# PDM_Final.net
KiCad netlist of a schematic drawn in EAGLE
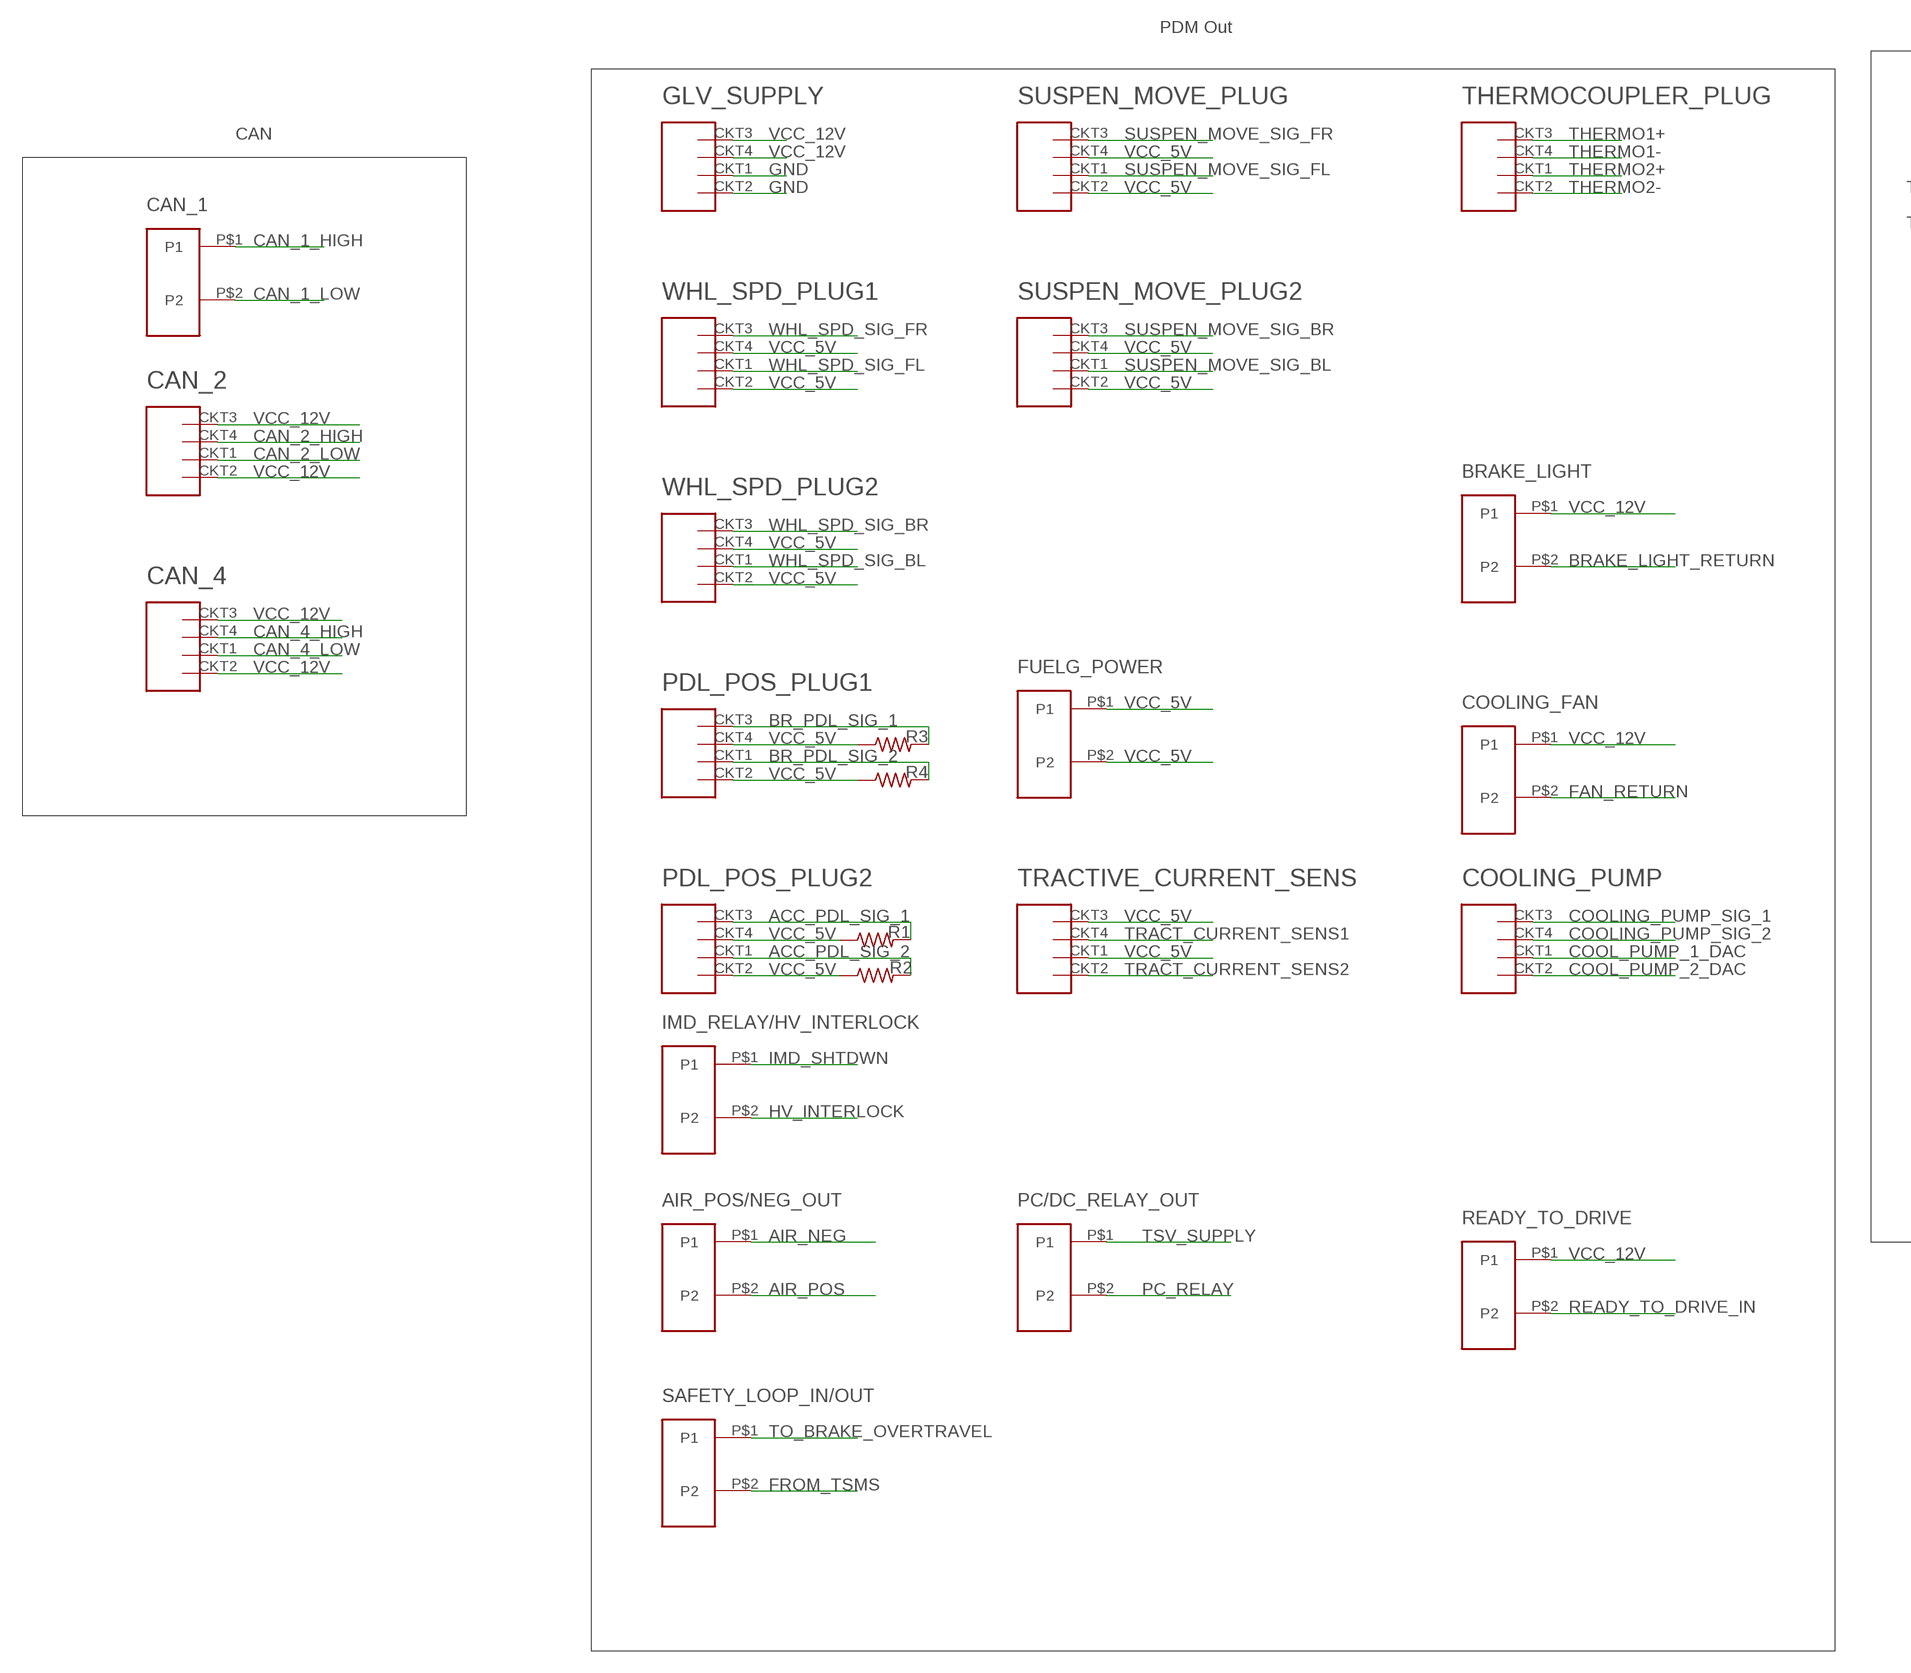
[diagram p0: schematic, sheet 1, part 1 of 2]
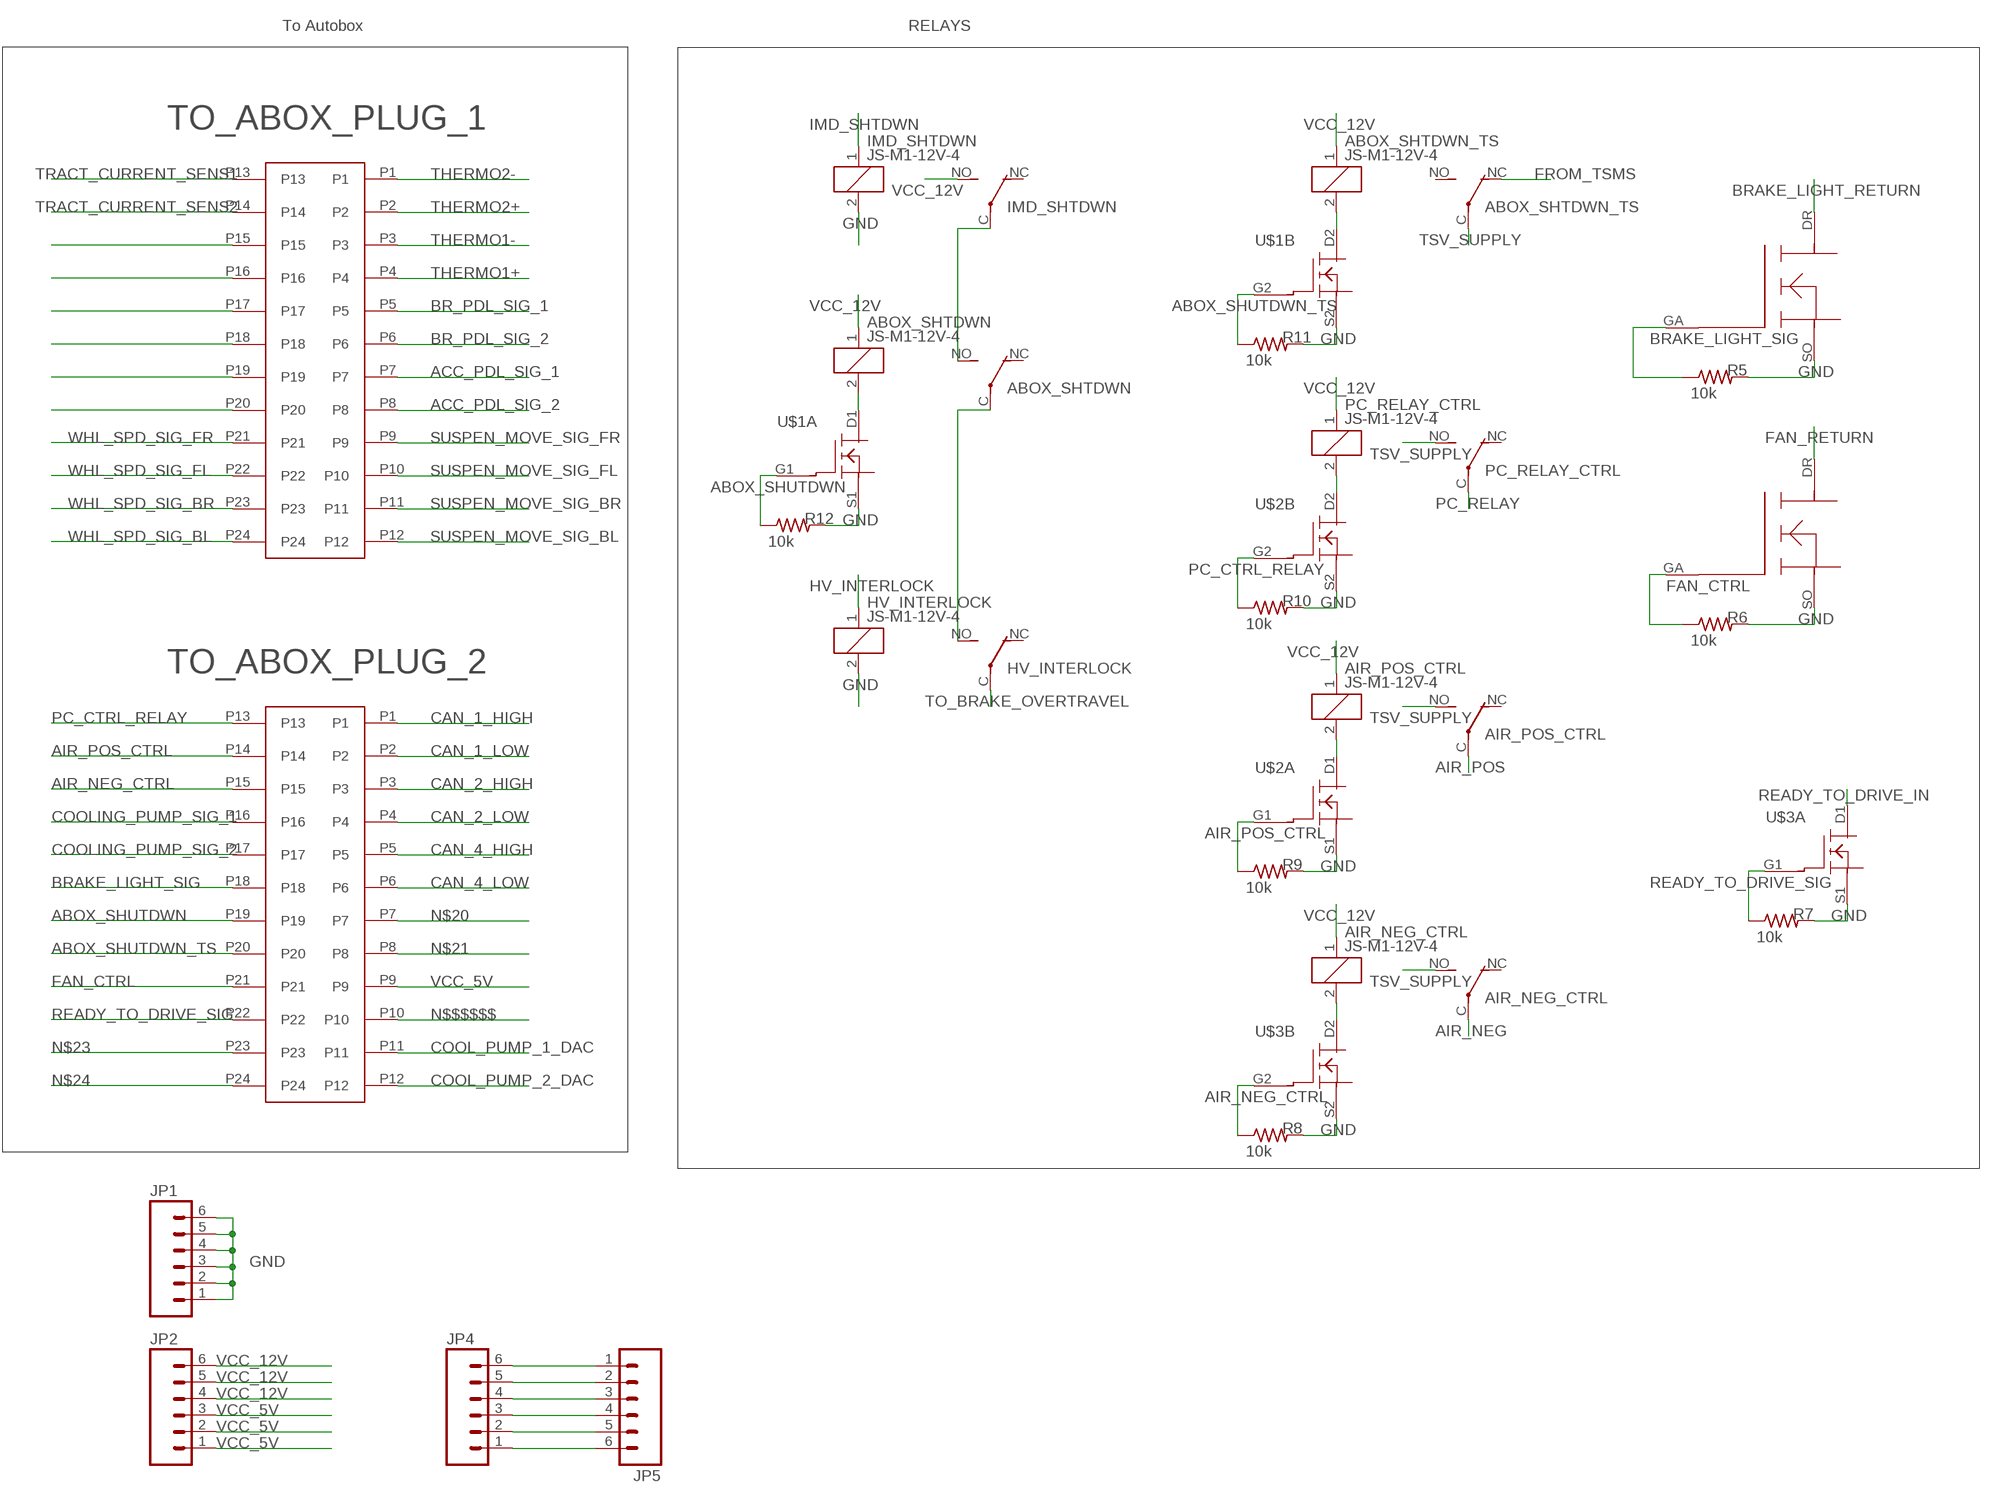
[diagram p1: schematic, sheet 1, part 2 of 2]

(export (version "E")
  (design (tool "Eeschema 10.0.6"))
  (components
    (comp (ref "ABOX_SHTDWN")
      (value "JS-M1-12V-4")
      (footprint "eagle-import:JS-M")
      (fields (field (name "MPN") "JSM1-12V-4"))
      (libsource (lib "eagle-import") (part "JS-M1-12V-4"))
    )
    (comp (ref "ABOX_SHTDWN_TS")
      (value "JS-M1-12V-4")
      (footprint "eagle-import:JS-M")
      (fields (field (name "MPN") "JSM1-12V-4"))
      (libsource (lib "eagle-import") (part "JS-M1-12V-4"))
    )
    (comp (ref "AIR_NEG_CTRL")
      (value "JS-M1-12V-4")
      (footprint "eagle-import:JS-M")
      (fields (field (name "MPN") "JSM1-12V-4"))
      (libsource (lib "eagle-import") (part "JS-M1-12V-4"))
    )
    (comp (ref "AIR_POS/NEG_OUT")
      (value "MINIFIT_2PIN")
      (footprint "eagle-import:2PIN_MOLEXMINIFIT")
      (libsource (lib "eagle-import") (part "MINIFIT_2PIN"))
    )
    (comp (ref "AIR_POS_CTRL")
      (value "JS-M1-12V-4")
      (footprint "eagle-import:JS-M")
      (fields (field (name "MPN") "JSM1-12V-4"))
      (libsource (lib "eagle-import") (part "JS-M1-12V-4"))
    )
    (comp (ref "BRAKE_LIGHT")
      (value "MINIFIT_2PIN")
      (footprint "eagle-import:2PIN_MOLEXMINIFIT")
      (libsource (lib "eagle-import") (part "MINIFIT_2PIN"))
    )
    (comp (ref "CAN_1")
      (value "MINIFIT_2PIN")
      (footprint "eagle-import:2PIN_MOLEXMINIFIT")
      (libsource (lib "eagle-import") (part "MINIFIT_2PIN"))
    )
    (comp (ref "CAN_2")
      (value "MHYBRIDMOLEX")
      (footprint "eagle-import:MOLEXMINIFIT6")
      (libsource (lib "eagle-import") (part "MHYBRIDMOLEX"))
    )
    (comp (ref "CAN_4")
      (value "MHYBRIDMOLEX")
      (footprint "eagle-import:MOLEXMINIFIT6")
      (libsource (lib "eagle-import") (part "MHYBRIDMOLEX"))
    )
    (comp (ref "COOLING_FAN")
      (value "MINIFIT_2PIN")
      (footprint "eagle-import:2PIN_MOLEXMINIFIT")
      (libsource (lib "eagle-import") (part "MINIFIT_2PIN"))
    )
    (comp (ref "COOLING_PUMP")
      (value "MHYBRIDMOLEX")
      (footprint "eagle-import:MOLEXMINIFIT6")
      (libsource (lib "eagle-import") (part "MHYBRIDMOLEX"))
    )
    (comp (ref "FUELG_POWER")
      (value "MINIFIT_2PIN")
      (footprint "eagle-import:2PIN_MOLEXMINIFIT")
      (libsource (lib "eagle-import") (part "MINIFIT_2PIN"))
    )
    (comp (ref "GLV_SUPPLY")
      (value "MHYBRIDMOLEX")
      (footprint "eagle-import:MOLEXMINIFIT6")
      (libsource (lib "eagle-import") (part "MHYBRIDMOLEX"))
    )
    (comp (ref "HV_INTERLOCK")
      (value "JS-M1-12V-4")
      (footprint "eagle-import:JS-M")
      (fields (field (name "MPN") "JSM1-12V-4"))
      (libsource (lib "eagle-import") (part "JS-M1-12V-4"))
    )
    (comp (ref "IMD_RELAY/HV_INTERLOCK")
      (value "MINIFIT_2PIN")
      (footprint "eagle-import:2PIN_MOLEXMINIFIT")
      (libsource (lib "eagle-import") (part "MINIFIT_2PIN"))
    )
    (comp (ref "IMD_SHTDWN")
      (value "JS-M1-12V-4")
      (footprint "eagle-import:JS-M")
      (fields (field (name "MPN") "JSM1-12V-4"))
      (libsource (lib "eagle-import") (part "JS-M1-12V-4"))
    )
    (comp (ref "JP1")
      (value "M06LOCK")
      (footprint "eagle-import:1X06_LOCK")
      (libsource (lib "eagle-import") (part "M06LOCK"))
    )
    (comp (ref "JP2")
      (value "M06LOCK")
      (footprint "eagle-import:1X06_LOCK")
      (libsource (lib "eagle-import") (part "M06LOCK"))
    )
    (comp (ref "JP4")
      (value "M06LOCK")
      (footprint "eagle-import:1X06_LOCK")
      (libsource (lib "eagle-import") (part "M06LOCK"))
    )
    (comp (ref "JP5")
      (value "M06LOCK")
      (footprint "eagle-import:1X06_LOCK")
      (libsource (lib "eagle-import") (part "M06LOCK"))
    )
    (comp (ref "PC/DC_RELAY_OUT")
      (value "MINIFIT_2PIN")
      (footprint "eagle-import:2PIN_MOLEXMINIFIT")
      (libsource (lib "eagle-import") (part "MINIFIT_2PIN"))
    )
    (comp (ref "PC_RELAY_CTRL")
      (value "JS-M1-12V-4")
      (footprint "eagle-import:JS-M")
      (fields (field (name "MPN") "JSM1-12V-4"))
      (libsource (lib "eagle-import") (part "JS-M1-12V-4"))
    )
    (comp (ref "PDL_POS_PLUG1")
      (value "MHYBRIDMOLEX")
      (footprint "eagle-import:MOLEXMINIFIT6")
      (libsource (lib "eagle-import") (part "MHYBRIDMOLEX"))
    )
    (comp (ref "PDL_POS_PLUG2")
      (value "MHYBRIDMOLEX")
      (footprint "eagle-import:MOLEXMINIFIT6")
      (libsource (lib "eagle-import") (part "MHYBRIDMOLEX"))
    )
    (comp (ref "R1")
      (value "R-US_0204/2V")
      (footprint "eagle-import:0204V")
      (libsource (lib "eagle-import") (part "R-US_0204/2V"))
    )
    (comp (ref "R2")
      (value "R-US_0204/2V")
      (footprint "eagle-import:0204V")
      (libsource (lib "eagle-import") (part "R-US_0204/2V"))
    )
    (comp (ref "R3")
      (value "R-US_0204/2V")
      (footprint "eagle-import:0204V")
      (libsource (lib "eagle-import") (part "R-US_0204/2V"))
    )
    (comp (ref "R4")
      (value "R-US_0204/2V")
      (footprint "eagle-import:0204V")
      (libsource (lib "eagle-import") (part "R-US_0204/2V"))
    )
    (comp (ref "R5")
      (value "10k")
      (footprint "eagle-import:0204V")
      (libsource (lib "eagle-import") (part "R-US_0204/2V"))
    )
    (comp (ref "R6")
      (value "10k")
      (footprint "eagle-import:0204V")
      (libsource (lib "eagle-import") (part "R-US_0204/2V"))
    )
    (comp (ref "R7")
      (value "10k")
      (footprint "eagle-import:0204V")
      (libsource (lib "eagle-import") (part "R-US_0204/2V"))
    )
    (comp (ref "R8")
      (value "10k")
      (footprint "eagle-import:0204V")
      (libsource (lib "eagle-import") (part "R-US_0204/2V"))
    )
    (comp (ref "R9")
      (value "10k")
      (footprint "eagle-import:0204V")
      (libsource (lib "eagle-import") (part "R-US_0204/2V"))
    )
    (comp (ref "R10")
      (value "10k")
      (footprint "eagle-import:0204V")
      (libsource (lib "eagle-import") (part "R-US_0204/2V"))
    )
    (comp (ref "R11")
      (value "10k")
      (footprint "eagle-import:0204V")
      (libsource (lib "eagle-import") (part "R-US_0204/2V"))
    )
    (comp (ref "R12")
      (value "10k")
      (footprint "eagle-import:0204V")
      (libsource (lib "eagle-import") (part "R-US_0204/2V"))
    )
    (comp (ref "READY_TO_DRIVE")
      (value "MINIFIT_2PIN")
      (footprint "eagle-import:2PIN_MOLEXMINIFIT")
      (libsource (lib "eagle-import") (part "MINIFIT_2PIN"))
    )
    (comp (ref "SAFETY_LOOP_IN/OUT")
      (value "MINIFIT_2PIN")
      (footprint "eagle-import:2PIN_MOLEXMINIFIT")
      (libsource (lib "eagle-import") (part "MINIFIT_2PIN"))
    )
    (comp (ref "SUSPEN_MOVE_PLUG")
      (value "MHYBRIDMOLEX")
      (footprint "eagle-import:MOLEXMINIFIT6")
      (libsource (lib "eagle-import") (part "MHYBRIDMOLEX"))
    )
    (comp (ref "SUSPEN_MOVE_PLUG2")
      (value "MHYBRIDMOLEX")
      (footprint "eagle-import:MOLEXMINIFIT6")
      (libsource (lib "eagle-import") (part "MHYBRIDMOLEX"))
    )
    (comp (ref "THERMOCOUPLER_PLUG")
      (value "MHYBRIDMOLEX")
      (footprint "eagle-import:MOLEXMINIFIT6")
      (libsource (lib "eagle-import") (part "MHYBRIDMOLEX"))
    )
    (comp (ref "TO_ABOX_PLUG_1")
      (value "24PIN_MOLEX")
      (footprint "eagle-import:24PIN_MOLEX")
      (libsource (lib "eagle-import") (part "24PIN_MOLEX"))
    )
    (comp (ref "TO_ABOX_PLUG_2")
      (value "24PIN_MOLEX")
      (footprint "eagle-import:24PIN_MOLEX")
      (libsource (lib "eagle-import") (part "24PIN_MOLEX"))
    )
    (comp (ref "TRACTIVE_CURRENT_SENS")
      (value "MHYBRIDMOLEX")
      (footprint "eagle-import:MOLEXMINIFIT6")
      (libsource (lib "eagle-import") (part "MHYBRIDMOLEX"))
    )
    (comp (ref "U$1")
      (value "COMBINED_TRANSIS")
      (footprint "eagle-import:TRANSIS_6")
      (libsource (lib "eagle-import") (part "COMBINED_TRANSIS"))
    )
    (comp (ref "U$2")
      (value "COMBINED_TRANSIS")
      (footprint "eagle-import:TRANSIS_6")
      (libsource (lib "eagle-import") (part "COMBINED_TRANSIS"))
    )
    (comp (ref "U$3")
      (value "COMBINED_TRANSIS")
      (footprint "eagle-import:TRANSIS_6")
      (libsource (lib "eagle-import") (part "COMBINED_TRANSIS"))
    )
    (comp (ref "U$4")
      (value "HIGH_AMP_TRANS")
      (footprint "eagle-import:HIGH_AMP_TRANS")
      (libsource (lib "eagle-import") (part "HIGH_AMP_TRANS"))
    )
    (comp (ref "U$5")
      (value "HIGH_AMP_TRANS")
      (footprint "eagle-import:HIGH_AMP_TRANS")
      (libsource (lib "eagle-import") (part "HIGH_AMP_TRANS"))
    )
    (comp (ref "WHL_SPD_PLUG1")
      (value "MHYBRIDMOLEX")
      (footprint "eagle-import:MOLEXMINIFIT6")
      (libsource (lib "eagle-import") (part "MHYBRIDMOLEX"))
    )
    (comp (ref "WHL_SPD_PLUG2")
      (value "MHYBRIDMOLEX")
      (footprint "eagle-import:MOLEXMINIFIT6")
      (libsource (lib "eagle-import") (part "MHYBRIDMOLEX"))
    )
  )
  (nets
    (net (code "1") (name "/ABOX_SHUTDWN") (class "Default")
      (node (ref "R12") (pin "1") (pinfunction "1_1") (pintype "passive"))
      (node (ref "TO_ABOX_PLUG_2") (pin "P19") (pinfunction "P19_P19") (pintype "bidirectional"))
      (node (ref "U$1") (pin "G1") (pinfunction "GA_G1") (pintype "bidirectional"))
    )
    (net (code "2") (name "/ABOX_SHUTDWN_TS") (class "Default")
      (node (ref "R11") (pin "1") (pinfunction "1_1") (pintype "passive"))
      (node (ref "TO_ABOX_PLUG_2") (pin "P20") (pinfunction "P20_P20") (pintype "bidirectional"))
      (node (ref "U$1") (pin "G2") (pinfunction "GA_G2") (pintype "bidirectional"))
    )
    (net (code "3") (name "/ACC_PDL_SIG_1") (class "Default")
      (node (ref "PDL_POS_PLUG2") (pin "CKT3") (pinfunction "V_IN(12)_CKT3") (pintype "bidirectional"))
      (node (ref "R1") (pin "2") (pinfunction "2_2") (pintype "passive"))
      (node (ref "TO_ABOX_PLUG_1") (pin "P7") (pinfunction "P7_P7") (pintype "bidirectional"))
    )
    (net (code "4") (name "/ACC_PDL_SIG_2") (class "Default")
      (node (ref "PDL_POS_PLUG2") (pin "CKT1") (pinfunction "GND_CKT1") (pintype "bidirectional"))
      (node (ref "R2") (pin "2") (pinfunction "2_2") (pintype "passive"))
      (node (ref "TO_ABOX_PLUG_1") (pin "P8") (pinfunction "P8_P8") (pintype "bidirectional"))
    )
    (net (code "5") (name "/AIR_NEG") (class "Default")
      (node (ref "AIR_NEG_CTRL") (pin "C") (pinfunction "P_C") (pintype "passive"))
      (node (ref "AIR_POS/NEG_OUT") (pin "P$1") (pinfunction "P1_P$1") (pintype "bidirectional"))
    )
    (net (code "6") (name "/AIR_NEG_CTRL") (class "Default")
      (node (ref "R8") (pin "1") (pinfunction "1_1") (pintype "passive"))
      (node (ref "TO_ABOX_PLUG_2") (pin "P15") (pinfunction "P15_P15") (pintype "bidirectional"))
      (node (ref "U$3") (pin "G2") (pinfunction "GA_G2") (pintype "bidirectional"))
    )
    (net (code "7") (name "/AIR_POS") (class "Default")
      (node (ref "AIR_POS/NEG_OUT") (pin "P$2") (pinfunction "P2_P$2") (pintype "bidirectional"))
      (node (ref "AIR_POS_CTRL") (pin "C") (pinfunction "P_C") (pintype "passive"))
    )
    (net (code "8") (name "/AIR_POS_CTRL") (class "Default")
      (node (ref "R9") (pin "1") (pinfunction "1_1") (pintype "passive"))
      (node (ref "TO_ABOX_PLUG_2") (pin "P14") (pinfunction "P14_P14") (pintype "bidirectional"))
      (node (ref "U$2") (pin "G1") (pinfunction "GA_G1") (pintype "bidirectional"))
    )
    (net (code "9") (name "/BRAKE_LIGHT_RETURN") (class "Default")
      (node (ref "BRAKE_LIGHT") (pin "P$2") (pinfunction "P2_P$2") (pintype "bidirectional"))
      (node (ref "U$4") (pin "DR") (pinfunction "DR_DR") (pintype "bidirectional"))
    )
    (net (code "10") (name "/BRAKE_LIGHT_SIG") (class "Default")
      (node (ref "R5") (pin "1") (pinfunction "1_1") (pintype "passive"))
      (node (ref "TO_ABOX_PLUG_2") (pin "P18") (pinfunction "P18_P18") (pintype "bidirectional"))
      (node (ref "U$4") (pin "GA") (pinfunction "GA_GA") (pintype "bidirectional"))
    )
    (net (code "11") (name "/BR_PDL_SIG_1") (class "Default")
      (node (ref "PDL_POS_PLUG1") (pin "CKT3") (pinfunction "V_IN(12)_CKT3") (pintype "bidirectional"))
      (node (ref "R3") (pin "2") (pinfunction "2_2") (pintype "passive"))
      (node (ref "TO_ABOX_PLUG_1") (pin "P5") (pinfunction "P5_P5") (pintype "bidirectional"))
    )
    (net (code "12") (name "/BR_PDL_SIG_2") (class "Default")
      (node (ref "PDL_POS_PLUG1") (pin "CKT1") (pinfunction "GND_CKT1") (pintype "bidirectional"))
      (node (ref "R4") (pin "2") (pinfunction "2_2") (pintype "passive"))
      (node (ref "TO_ABOX_PLUG_1") (pin "P6") (pinfunction "P6_P6") (pintype "bidirectional"))
    )
    (net (code "13") (name "/CAN_1_HIGH") (class "Default")
      (node (ref "CAN_1") (pin "P$1") (pinfunction "P1_P$1") (pintype "bidirectional"))
      (node (ref "TO_ABOX_PLUG_2") (pin "P1") (pinfunction "P1_P1") (pintype "bidirectional"))
    )
    (net (code "14") (name "/CAN_1_LOW") (class "Default")
      (node (ref "CAN_1") (pin "P$2") (pinfunction "P2_P$2") (pintype "bidirectional"))
      (node (ref "TO_ABOX_PLUG_2") (pin "P2") (pinfunction "P2_P2") (pintype "bidirectional"))
    )
    (net (code "15") (name "/CAN_2_HIGH") (class "Default")
      (node (ref "CAN_2") (pin "CKT4") (pinfunction "V_IN2(12)_CKT4") (pintype "bidirectional"))
      (node (ref "TO_ABOX_PLUG_2") (pin "P3") (pinfunction "P3_P3") (pintype "bidirectional"))
    )
    (net (code "16") (name "/CAN_2_LOW") (class "Default")
      (node (ref "CAN_2") (pin "CKT1") (pinfunction "GND_CKT1") (pintype "bidirectional"))
      (node (ref "TO_ABOX_PLUG_2") (pin "P4") (pinfunction "P4_P4") (pintype "bidirectional"))
    )
    (net (code "17") (name "/CAN_4_HIGH") (class "Default")
      (node (ref "CAN_4") (pin "CKT4") (pinfunction "V_IN2(12)_CKT4") (pintype "bidirectional"))
      (node (ref "TO_ABOX_PLUG_2") (pin "P5") (pinfunction "P5_P5") (pintype "bidirectional"))
    )
    (net (code "18") (name "/CAN_4_LOW") (class "Default")
      (node (ref "CAN_4") (pin "CKT1") (pinfunction "GND_CKT1") (pintype "bidirectional"))
      (node (ref "TO_ABOX_PLUG_2") (pin "P6") (pinfunction "P6_P6") (pintype "bidirectional"))
    )
    (net (code "19") (name "/COOLING_PUMP_SIG_1") (class "Default")
      (node (ref "COOLING_PUMP") (pin "CKT3") (pinfunction "V_IN(12)_CKT3") (pintype "bidirectional"))
      (node (ref "TO_ABOX_PLUG_2") (pin "P16") (pinfunction "P16_P16") (pintype "bidirectional"))
    )
    (net (code "20") (name "/COOLING_PUMP_SIG_2") (class "Default")
      (node (ref "COOLING_PUMP") (pin "CKT4") (pinfunction "V_IN2(12)_CKT4") (pintype "bidirectional"))
      (node (ref "TO_ABOX_PLUG_2") (pin "P17") (pinfunction "P17_P17") (pintype "bidirectional"))
    )
    (net (code "21") (name "/COOL_PUMP_1_DAC") (class "Default")
      (node (ref "COOLING_PUMP") (pin "CKT1") (pinfunction "GND_CKT1") (pintype "bidirectional"))
      (node (ref "TO_ABOX_PLUG_2") (pin "P11") (pinfunction "P11_P11") (pintype "bidirectional"))
    )
    (net (code "22") (name "/COOL_PUMP_2_DAC") (class "Default")
      (node (ref "COOLING_PUMP") (pin "CKT2") (pinfunction "GND2_CKT2") (pintype "bidirectional"))
      (node (ref "TO_ABOX_PLUG_2") (pin "P12") (pinfunction "P12_P12") (pintype "bidirectional"))
    )
    (net (code "23") (name "/FAN_CTRL") (class "Default")
      (node (ref "R6") (pin "1") (pinfunction "1_1") (pintype "passive"))
      (node (ref "TO_ABOX_PLUG_2") (pin "P21") (pinfunction "P21_P21") (pintype "bidirectional"))
      (node (ref "U$5") (pin "GA") (pinfunction "GA_GA") (pintype "bidirectional"))
    )
    (net (code "24") (name "/FAN_RETURN") (class "Default")
      (node (ref "COOLING_FAN") (pin "P$2") (pinfunction "P2_P$2") (pintype "bidirectional"))
      (node (ref "U$5") (pin "DR") (pinfunction "DR_DR") (pintype "bidirectional"))
    )
    (net (code "25") (name "/FROM_TSMS") (class "Default")
      (node (ref "ABOX_SHTDWN_TS") (pin "NC") (pinfunction "O_NC") (pintype "passive"))
      (node (ref "SAFETY_LOOP_IN/OUT") (pin "P$2") (pinfunction "P2_P$2") (pintype "bidirectional"))
    )
    (net (code "26") (name "/GND") (class "Default")
      (node (ref "GLV_SUPPLY") (pin "CKT1") (pinfunction "GND_CKT1") (pintype "bidirectional"))
      (node (ref "GLV_SUPPLY") (pin "CKT2") (pinfunction "GND2_CKT2") (pintype "bidirectional"))
      (node (ref "HV_INTERLOCK") (pin "2") (pinfunction "2_2") (pintype "passive"))
      (node (ref "IMD_SHTDWN") (pin "2") (pinfunction "2_2") (pintype "passive"))
      (node (ref "JP1") (pin "1") (pinfunction "1_1") (pintype "passive"))
      (node (ref "JP1") (pin "2") (pinfunction "2_2") (pintype "passive"))
      (node (ref "JP1") (pin "3") (pinfunction "3_3") (pintype "passive"))
      (node (ref "JP1") (pin "4") (pinfunction "4_4") (pintype "passive"))
      (node (ref "JP1") (pin "5") (pinfunction "5_5") (pintype "passive"))
      (node (ref "JP1") (pin "6") (pinfunction "6_6") (pintype "passive"))
      (node (ref "R10") (pin "2") (pinfunction "2_2") (pintype "passive"))
      (node (ref "R11") (pin "2") (pinfunction "2_2") (pintype "passive"))
      (node (ref "R12") (pin "2") (pinfunction "2_2") (pintype "passive"))
      (node (ref "R5") (pin "2") (pinfunction "2_2") (pintype "passive"))
      (node (ref "R6") (pin "2") (pinfunction "2_2") (pintype "passive"))
      (node (ref "R7") (pin "2") (pinfunction "2_2") (pintype "passive"))
      (node (ref "R8") (pin "2") (pinfunction "2_2") (pintype "passive"))
      (node (ref "R9") (pin "2") (pinfunction "2_2") (pintype "passive"))
      (node (ref "U$1") (pin "S1") (pinfunction "SO_S1") (pintype "bidirectional"))
      (node (ref "U$1") (pin "S2") (pinfunction "SO_S2") (pintype "bidirectional"))
      (node (ref "U$2") (pin "S1") (pinfunction "SO_S1") (pintype "bidirectional"))
      (node (ref "U$2") (pin "S2") (pinfunction "SO_S2") (pintype "bidirectional"))
      (node (ref "U$3") (pin "S1") (pinfunction "SO_S1") (pintype "bidirectional"))
      (node (ref "U$3") (pin "S2") (pinfunction "SO_S2") (pintype "bidirectional"))
      (node (ref "U$4") (pin "SO") (pinfunction "SO_SO") (pintype "bidirectional"))
      (node (ref "U$5") (pin "SO") (pinfunction "SO_SO") (pintype "bidirectional"))
    )
    (net (code "27") (name "/HV_INTERLOCK") (class "Default")
      (node (ref "HV_INTERLOCK") (pin "1") (pinfunction "1_1") (pintype "passive"))
      (node (ref "IMD_RELAY/HV_INTERLOCK") (pin "P$2") (pinfunction "P2_P$2") (pintype "bidirectional"))
    )
    (net (code "28") (name "/IMD_SHTDWN") (class "Default")
      (node (ref "IMD_RELAY/HV_INTERLOCK") (pin "P$1") (pinfunction "P1_P$1") (pintype "bidirectional"))
      (node (ref "IMD_SHTDWN") (pin "1") (pinfunction "1_1") (pintype "passive"))
    )
    (net (code "29") (name "/N$$$$$$") (class "Default")
      (node (ref "TO_ABOX_PLUG_2") (pin "P10") (pinfunction "P10_P10") (pintype "bidirectional"))
    )
    (net (code "30") (name "/N$20") (class "Default")
      (node (ref "TO_ABOX_PLUG_2") (pin "P7") (pinfunction "P7_P7") (pintype "bidirectional"))
    )
    (net (code "31") (name "/N$21") (class "Default")
      (node (ref "TO_ABOX_PLUG_2") (pin "P8") (pinfunction "P8_P8") (pintype "bidirectional"))
    )
    (net (code "32") (name "/N$23") (class "Default")
      (node (ref "TO_ABOX_PLUG_2") (pin "P23") (pinfunction "P23_P23") (pintype "bidirectional"))
    )
    (net (code "33") (name "/N$24") (class "Default")
      (node (ref "TO_ABOX_PLUG_2") (pin "P24") (pinfunction "P24_P24") (pintype "bidirectional"))
    )
    (net (code "34") (name "/PC_CTRL_RELAY") (class "Default")
      (node (ref "R10") (pin "1") (pinfunction "1_1") (pintype "passive"))
      (node (ref "TO_ABOX_PLUG_2") (pin "P13") (pinfunction "P13_P13") (pintype "bidirectional"))
      (node (ref "U$2") (pin "G2") (pinfunction "GA_G2") (pintype "bidirectional"))
    )
    (net (code "35") (name "/PC_RELAY") (class "Default")
      (node (ref "PC/DC_RELAY_OUT") (pin "P$2") (pinfunction "P2_P$2") (pintype "bidirectional"))
      (node (ref "PC_RELAY_CTRL") (pin "C") (pinfunction "P_C") (pintype "passive"))
    )
    (net (code "36") (name "/READY_TO_DRIVE_IN") (class "Default")
      (node (ref "READY_TO_DRIVE") (pin "P$2") (pinfunction "P2_P$2") (pintype "bidirectional"))
      (node (ref "U$3") (pin "D1") (pinfunction "DR_D1") (pintype "bidirectional"))
    )
    (net (code "37") (name "/READY_TO_DRIVE_SIG") (class "Default")
      (node (ref "R7") (pin "1") (pinfunction "1_1") (pintype "passive"))
      (node (ref "TO_ABOX_PLUG_2") (pin "P22") (pinfunction "P22_P22") (pintype "bidirectional"))
      (node (ref "U$3") (pin "G1") (pinfunction "GA_G1") (pintype "bidirectional"))
    )
    (net (code "38") (name "/SUSPEN_MOVE_SIG_BL") (class "Default")
      (node (ref "SUSPEN_MOVE_PLUG2") (pin "CKT1") (pinfunction "GND_CKT1") (pintype "bidirectional"))
      (node (ref "TO_ABOX_PLUG_1") (pin "P12") (pinfunction "P12_P12") (pintype "bidirectional"))
    )
    (net (code "39") (name "/SUSPEN_MOVE_SIG_BR") (class "Default")
      (node (ref "SUSPEN_MOVE_PLUG2") (pin "CKT3") (pinfunction "V_IN(12)_CKT3") (pintype "bidirectional"))
      (node (ref "TO_ABOX_PLUG_1") (pin "P11") (pinfunction "P11_P11") (pintype "bidirectional"))
    )
    (net (code "40") (name "/SUSPEN_MOVE_SIG_FL") (class "Default")
      (node (ref "SUSPEN_MOVE_PLUG") (pin "CKT1") (pinfunction "GND_CKT1") (pintype "bidirectional"))
      (node (ref "TO_ABOX_PLUG_1") (pin "P10") (pinfunction "P10_P10") (pintype "bidirectional"))
    )
    (net (code "41") (name "/SUSPEN_MOVE_SIG_FR") (class "Default")
      (node (ref "SUSPEN_MOVE_PLUG") (pin "CKT3") (pinfunction "V_IN(12)_CKT3") (pintype "bidirectional"))
      (node (ref "TO_ABOX_PLUG_1") (pin "P9") (pinfunction "P9_P9") (pintype "bidirectional"))
    )
    (net (code "42") (name "/THERMO1+") (class "Default")
      (node (ref "THERMOCOUPLER_PLUG") (pin "CKT3") (pinfunction "V_IN(12)_CKT3") (pintype "bidirectional"))
      (node (ref "TO_ABOX_PLUG_1") (pin "P4") (pinfunction "P4_P4") (pintype "bidirectional"))
    )
    (net (code "43") (name "/THERMO1-") (class "Default")
      (node (ref "THERMOCOUPLER_PLUG") (pin "CKT4") (pinfunction "V_IN2(12)_CKT4") (pintype "bidirectional"))
      (node (ref "TO_ABOX_PLUG_1") (pin "P3") (pinfunction "P3_P3") (pintype "bidirectional"))
    )
    (net (code "44") (name "/THERMO2+") (class "Default")
      (node (ref "THERMOCOUPLER_PLUG") (pin "CKT1") (pinfunction "GND_CKT1") (pintype "bidirectional"))
      (node (ref "TO_ABOX_PLUG_1") (pin "P2") (pinfunction "P2_P2") (pintype "bidirectional"))
    )
    (net (code "45") (name "/THERMO2-") (class "Default")
      (node (ref "THERMOCOUPLER_PLUG") (pin "CKT2") (pinfunction "GND2_CKT2") (pintype "bidirectional"))
      (node (ref "TO_ABOX_PLUG_1") (pin "P1") (pinfunction "P1_P1") (pintype "bidirectional"))
    )
    (net (code "46") (name "/TO_BRAKE_OVERTRAVEL") (class "Default")
      (node (ref "HV_INTERLOCK") (pin "C") (pinfunction "P_C") (pintype "passive"))
      (node (ref "SAFETY_LOOP_IN/OUT") (pin "P$1") (pinfunction "P1_P$1") (pintype "bidirectional"))
    )
    (net (code "47") (name "/TRACT_CURRENT_SENS1") (class "Default")
      (node (ref "TO_ABOX_PLUG_1") (pin "P13") (pinfunction "P13_P13") (pintype "bidirectional"))
      (node (ref "TRACTIVE_CURRENT_SENS") (pin "CKT4") (pinfunction "V_IN2(12)_CKT4") (pintype "bidirectional"))
    )
    (net (code "48") (name "/TRACT_CURRENT_SENS2") (class "Default")
      (node (ref "TO_ABOX_PLUG_1") (pin "P14") (pinfunction "P14_P14") (pintype "bidirectional"))
      (node (ref "TRACTIVE_CURRENT_SENS") (pin "CKT2") (pinfunction "GND2_CKT2") (pintype "bidirectional"))
    )
    (net (code "49") (name "/TSV_SUPPLY") (class "Default")
      (node (ref "ABOX_SHTDWN_TS") (pin "C") (pinfunction "P_C") (pintype "passive"))
      (node (ref "AIR_NEG_CTRL") (pin "NO") (pinfunction "S_NO") (pintype "passive"))
      (node (ref "AIR_POS_CTRL") (pin "NO") (pinfunction "S_NO") (pintype "passive"))
      (node (ref "PC/DC_RELAY_OUT") (pin "P$1") (pinfunction "P1_P$1") (pintype "bidirectional"))
      (node (ref "PC_RELAY_CTRL") (pin "NO") (pinfunction "S_NO") (pintype "passive"))
    )
    (net (code "50") (name "/VCC_5V") (class "Default")
      (node (ref "FUELG_POWER") (pin "P$1") (pinfunction "P1_P$1") (pintype "bidirectional"))
      (node (ref "FUELG_POWER") (pin "P$2") (pinfunction "P2_P$2") (pintype "bidirectional"))
      (node (ref "JP2") (pin "1") (pinfunction "1_1") (pintype "passive"))
      (node (ref "JP2") (pin "2") (pinfunction "2_2") (pintype "passive"))
      (node (ref "JP2") (pin "3") (pinfunction "3_3") (pintype "passive"))
      (node (ref "PDL_POS_PLUG1") (pin "CKT2") (pinfunction "GND2_CKT2") (pintype "bidirectional"))
      (node (ref "PDL_POS_PLUG1") (pin "CKT4") (pinfunction "V_IN2(12)_CKT4") (pintype "bidirectional"))
      (node (ref "PDL_POS_PLUG2") (pin "CKT2") (pinfunction "GND2_CKT2") (pintype "bidirectional"))
      (node (ref "PDL_POS_PLUG2") (pin "CKT4") (pinfunction "V_IN2(12)_CKT4") (pintype "bidirectional"))
      (node (ref "R1") (pin "1") (pinfunction "1_1") (pintype "passive"))
      (node (ref "R2") (pin "1") (pinfunction "1_1") (pintype "passive"))
      (node (ref "R3") (pin "1") (pinfunction "1_1") (pintype "passive"))
      (node (ref "R4") (pin "1") (pinfunction "1_1") (pintype "passive"))
      (node (ref "SUSPEN_MOVE_PLUG") (pin "CKT2") (pinfunction "GND2_CKT2") (pintype "bidirectional"))
      (node (ref "SUSPEN_MOVE_PLUG") (pin "CKT4") (pinfunction "V_IN2(12)_CKT4") (pintype "bidirectional"))
      (node (ref "SUSPEN_MOVE_PLUG2") (pin "CKT2") (pinfunction "GND2_CKT2") (pintype "bidirectional"))
      (node (ref "SUSPEN_MOVE_PLUG2") (pin "CKT4") (pinfunction "V_IN2(12)_CKT4") (pintype "bidirectional"))
      (node (ref "TO_ABOX_PLUG_2") (pin "P9") (pinfunction "P9_P9") (pintype "bidirectional"))
      (node (ref "TRACTIVE_CURRENT_SENS") (pin "CKT1") (pinfunction "GND_CKT1") (pintype "bidirectional"))
      (node (ref "TRACTIVE_CURRENT_SENS") (pin "CKT3") (pinfunction "V_IN(12)_CKT3") (pintype "bidirectional"))
      (node (ref "WHL_SPD_PLUG1") (pin "CKT2") (pinfunction "GND2_CKT2") (pintype "bidirectional"))
      (node (ref "WHL_SPD_PLUG1") (pin "CKT4") (pinfunction "V_IN2(12)_CKT4") (pintype "bidirectional"))
      (node (ref "WHL_SPD_PLUG2") (pin "CKT2") (pinfunction "GND2_CKT2") (pintype "bidirectional"))
      (node (ref "WHL_SPD_PLUG2") (pin "CKT4") (pinfunction "V_IN2(12)_CKT4") (pintype "bidirectional"))
    )
    (net (code "51") (name "/VCC_12V") (class "Default")
      (node (ref "ABOX_SHTDWN") (pin "1") (pinfunction "1_1") (pintype "passive"))
      (node (ref "ABOX_SHTDWN_TS") (pin "1") (pinfunction "1_1") (pintype "passive"))
      (node (ref "AIR_NEG_CTRL") (pin "1") (pinfunction "1_1") (pintype "passive"))
      (node (ref "AIR_POS_CTRL") (pin "1") (pinfunction "1_1") (pintype "passive"))
      (node (ref "BRAKE_LIGHT") (pin "P$1") (pinfunction "P1_P$1") (pintype "bidirectional"))
      (node (ref "CAN_2") (pin "CKT2") (pinfunction "GND2_CKT2") (pintype "bidirectional"))
      (node (ref "CAN_2") (pin "CKT3") (pinfunction "V_IN(12)_CKT3") (pintype "bidirectional"))
      (node (ref "CAN_4") (pin "CKT2") (pinfunction "GND2_CKT2") (pintype "bidirectional"))
      (node (ref "CAN_4") (pin "CKT3") (pinfunction "V_IN(12)_CKT3") (pintype "bidirectional"))
      (node (ref "COOLING_FAN") (pin "P$1") (pinfunction "P1_P$1") (pintype "bidirectional"))
      (node (ref "GLV_SUPPLY") (pin "CKT3") (pinfunction "V_IN(12)_CKT3") (pintype "bidirectional"))
      (node (ref "GLV_SUPPLY") (pin "CKT4") (pinfunction "V_IN2(12)_CKT4") (pintype "bidirectional"))
      (node (ref "IMD_SHTDWN") (pin "NO") (pinfunction "S_NO") (pintype "passive"))
      (node (ref "JP2") (pin "4") (pinfunction "4_4") (pintype "passive"))
      (node (ref "JP2") (pin "5") (pinfunction "5_5") (pintype "passive"))
      (node (ref "JP2") (pin "6") (pinfunction "6_6") (pintype "passive"))
      (node (ref "PC_RELAY_CTRL") (pin "1") (pinfunction "1_1") (pintype "passive"))
      (node (ref "READY_TO_DRIVE") (pin "P$1") (pinfunction "P1_P$1") (pintype "bidirectional"))
    )
    (net (code "52") (name "/WHL_SPD_SIG_BL") (class "Default")
      (node (ref "TO_ABOX_PLUG_1") (pin "P24") (pinfunction "P24_P24") (pintype "bidirectional"))
      (node (ref "WHL_SPD_PLUG2") (pin "CKT1") (pinfunction "GND_CKT1") (pintype "bidirectional"))
    )
    (net (code "53") (name "/WHL_SPD_SIG_BR") (class "Default")
      (node (ref "TO_ABOX_PLUG_1") (pin "P23") (pinfunction "P23_P23") (pintype "bidirectional"))
      (node (ref "WHL_SPD_PLUG2") (pin "CKT3") (pinfunction "V_IN(12)_CKT3") (pintype "bidirectional"))
    )
    (net (code "54") (name "/WHL_SPD_SIG_FL") (class "Default")
      (node (ref "TO_ABOX_PLUG_1") (pin "P22") (pinfunction "P22_P22") (pintype "bidirectional"))
      (node (ref "WHL_SPD_PLUG1") (pin "CKT1") (pinfunction "GND_CKT1") (pintype "bidirectional"))
    )
    (net (code "55") (name "/WHL_SPD_SIG_FR") (class "Default")
      (node (ref "TO_ABOX_PLUG_1") (pin "P21") (pinfunction "P21_P21") (pintype "bidirectional"))
      (node (ref "WHL_SPD_PLUG1") (pin "CKT3") (pinfunction "V_IN(12)_CKT3") (pintype "bidirectional"))
    )
    (net (code "56") (name "Net-(ABOX_SHTDWNB-P)") (class "Default")
      (node (ref "ABOX_SHTDWN") (pin "C") (pinfunction "P_C") (pintype "passive"))
      (node (ref "HV_INTERLOCK") (pin "NO") (pinfunction "S_NO") (pintype "passive"))
    )
    (net (code "57") (name "Net-(ABOX_SHTDWNB-S)") (class "Default")
      (node (ref "ABOX_SHTDWN") (pin "NO") (pinfunction "S_NO") (pintype "passive"))
      (node (ref "IMD_SHTDWN") (pin "C") (pinfunction "P_C") (pintype "passive"))
    )
    (net (code "58") (name "Net-(JP4-Pad1)") (class "Default")
      (node (ref "JP4") (pin "1") (pinfunction "1_1") (pintype "passive"))
      (node (ref "JP5") (pin "6") (pinfunction "6_6") (pintype "passive"))
    )
    (net (code "59") (name "Net-(JP4-Pad2)") (class "Default")
      (node (ref "JP4") (pin "2") (pinfunction "2_2") (pintype "passive"))
      (node (ref "JP5") (pin "5") (pinfunction "5_5") (pintype "passive"))
    )
    (net (code "60") (name "Net-(JP4-Pad3)") (class "Default")
      (node (ref "JP4") (pin "3") (pinfunction "3_3") (pintype "passive"))
      (node (ref "JP5") (pin "4") (pinfunction "4_4") (pintype "passive"))
    )
    (net (code "61") (name "Net-(JP4-Pad4)") (class "Default")
      (node (ref "JP4") (pin "4") (pinfunction "4_4") (pintype "passive"))
      (node (ref "JP5") (pin "3") (pinfunction "3_3") (pintype "passive"))
    )
    (net (code "62") (name "Net-(JP4-Pad5)") (class "Default")
      (node (ref "JP4") (pin "5") (pinfunction "5_5") (pintype "passive"))
      (node (ref "JP5") (pin "2") (pinfunction "2_2") (pintype "passive"))
    )
    (net (code "63") (name "Net-(JP4-Pad6)") (class "Default")
      (node (ref "JP4") (pin "6") (pinfunction "6_6") (pintype "passive"))
      (node (ref "JP5") (pin "1") (pinfunction "1_1") (pintype "passive"))
    )
    (net (code "64") (name "Net-(U$1A-DR)") (class "Default")
      (node (ref "ABOX_SHTDWN") (pin "2") (pinfunction "2_2") (pintype "passive"))
      (node (ref "U$1") (pin "D1") (pinfunction "DR_D1") (pintype "bidirectional"))
    )
    (net (code "65") (name "Net-(U$1B-DR)") (class "Default")
      (node (ref "ABOX_SHTDWN_TS") (pin "2") (pinfunction "2_2") (pintype "passive"))
      (node (ref "U$1") (pin "D2") (pinfunction "DR_D2") (pintype "bidirectional"))
    )
    (net (code "66") (name "Net-(U$2A-DR)") (class "Default")
      (node (ref "AIR_POS_CTRL") (pin "2") (pinfunction "2_2") (pintype "passive"))
      (node (ref "U$2") (pin "D1") (pinfunction "DR_D1") (pintype "bidirectional"))
    )
    (net (code "67") (name "Net-(U$2B-DR)") (class "Default")
      (node (ref "PC_RELAY_CTRL") (pin "2") (pinfunction "2_2") (pintype "passive"))
      (node (ref "U$2") (pin "D2") (pinfunction "DR_D2") (pintype "bidirectional"))
    )
    (net (code "68") (name "Net-(U$3B-DR)") (class "Default")
      (node (ref "AIR_NEG_CTRL") (pin "2") (pinfunction "2_2") (pintype "passive"))
      (node (ref "U$3") (pin "D2") (pinfunction "DR_D2") (pintype "bidirectional"))
    )
    (net (code "69") (name "unconnected-(ABOX_SHTDWNB-O-PadNC)") (class "Default")
      (node (ref "ABOX_SHTDWN") (pin "NC") (pinfunction "O_NC") (pintype "passive"))
    )
    (net (code "70") (name "unconnected-(ABOX_SHTDWN_TSB-S-PadNO)") (class "Default")
      (node (ref "ABOX_SHTDWN_TS") (pin "NO") (pinfunction "S_NO") (pintype "passive"))
    )
    (net (code "71") (name "unconnected-(AIR_NEG_CTRLB-O-PadNC)") (class "Default")
      (node (ref "AIR_NEG_CTRL") (pin "NC") (pinfunction "O_NC") (pintype "passive"))
    )
    (net (code "72") (name "unconnected-(AIR_POS_CTRLB-O-PadNC)") (class "Default")
      (node (ref "AIR_POS_CTRL") (pin "NC") (pinfunction "O_NC") (pintype "passive"))
    )
    (net (code "73") (name "unconnected-(HV_INTERLOCKB-O-PadNC)") (class "Default")
      (node (ref "HV_INTERLOCK") (pin "NC") (pinfunction "O_NC") (pintype "passive"))
    )
    (net (code "74") (name "unconnected-(IMD_SHTDWNB-O-PadNC)") (class "Default")
      (node (ref "IMD_SHTDWN") (pin "NC") (pinfunction "O_NC") (pintype "passive"))
    )
    (net (code "75") (name "unconnected-(PC_RELAY_CTRLB-O-PadNC)") (class "Default")
      (node (ref "PC_RELAY_CTRL") (pin "NC") (pinfunction "O_NC") (pintype "passive"))
    )
    (net (code "76") (name "unconnected-(TO_ABOX_PLUG_1-PadP15)") (class "Default")
      (node (ref "TO_ABOX_PLUG_1") (pin "P15") (pinfunction "P15_P15") (pintype "bidirectional"))
    )
    (net (code "77") (name "unconnected-(TO_ABOX_PLUG_1-PadP16)") (class "Default")
      (node (ref "TO_ABOX_PLUG_1") (pin "P16") (pinfunction "P16_P16") (pintype "bidirectional"))
    )
    (net (code "78") (name "unconnected-(TO_ABOX_PLUG_1-PadP17)") (class "Default")
      (node (ref "TO_ABOX_PLUG_1") (pin "P17") (pinfunction "P17_P17") (pintype "bidirectional"))
    )
    (net (code "79") (name "unconnected-(TO_ABOX_PLUG_1-PadP18)") (class "Default")
      (node (ref "TO_ABOX_PLUG_1") (pin "P18") (pinfunction "P18_P18") (pintype "bidirectional"))
    )
    (net (code "80") (name "unconnected-(TO_ABOX_PLUG_1-PadP19)") (class "Default")
      (node (ref "TO_ABOX_PLUG_1") (pin "P19") (pinfunction "P19_P19") (pintype "bidirectional"))
    )
    (net (code "81") (name "unconnected-(TO_ABOX_PLUG_1-PadP20)") (class "Default")
      (node (ref "TO_ABOX_PLUG_1") (pin "P20") (pinfunction "P20_P20") (pintype "bidirectional"))
    )
  )
)
